# Sheet1-control.net
KiCad netlist of a schematic drawn in Altium Designer
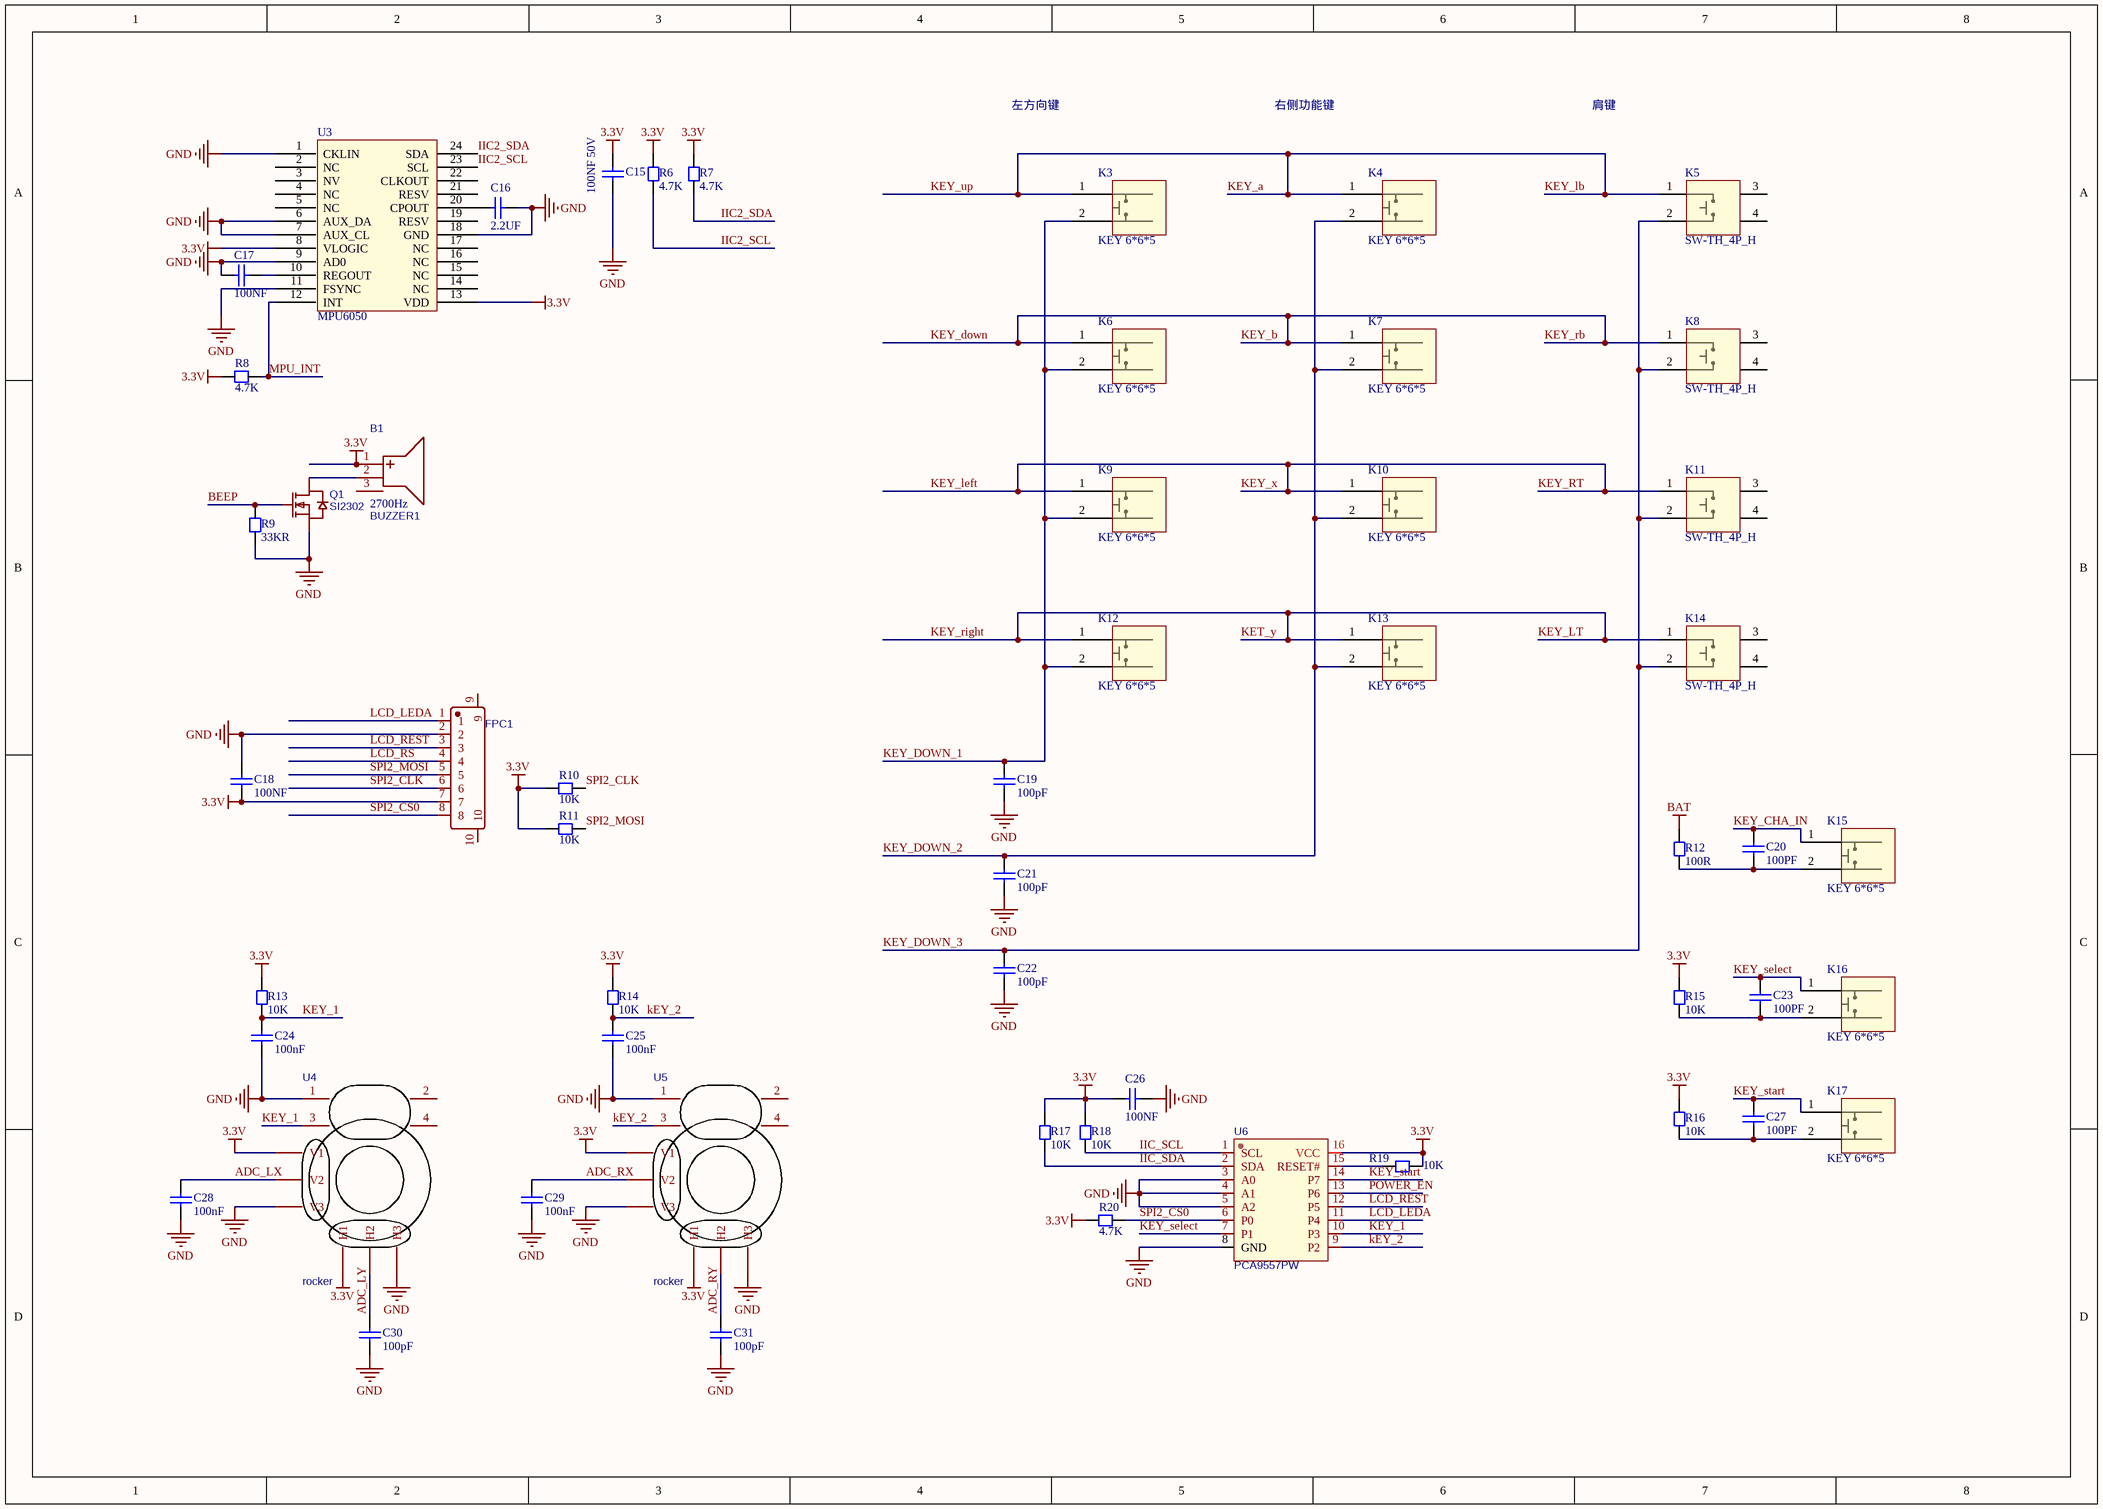
[diagram p0: Sheet1-control.SchDoc]

(export (version "E")
  (design (tool "Eeschema 10.0.6"))
  (components
    (comp (ref "B1")
      (value "BUZZER1")
      (footprint "BUZ-SMD_GSC7525RA")
      (description "2700Hz")
      (fields
        (field (name "MANUFACTURER") "INGHAi(赢海)")
        (field (name "MANUFACTURER PART") "GSC7525RA-16R2700")
        (field (name "CONTRIBUTOR") "LCSC")
      )
      (libsource (lib "base") (part "BUZZER1"))
    )
    (comp (ref "C15")
      (value "100NF 50V")
      (footprint "CC1608-0603")
      (description "0603封装的电容")
      (fields (field (name "PUBLISHER") "Altium Limited"))
      (libsource (lib "base") (part "Cap Chip 0603"))
    )
    (comp (ref "C16")
      (value "2.2UF")
      (footprint "CC1608-0603")
      (description "0603封装的电容")
      (fields (field (name "PUBLISHER") "Altium Limited"))
      (libsource (lib "base") (part "Cap Chip 0603"))
    )
    (comp (ref "C17")
      (value "100NF")
      (footprint "CC1608-0603")
      (description "0603封装的电容")
      (fields (field (name "PUBLISHER") "Altium Limited"))
      (libsource (lib "base") (part "Cap Chip 0603"))
    )
    (comp (ref "C18")
      (value "100NF")
      (footprint "CC1608-0603")
      (description "0603封装的电容")
      (fields (field (name "PUBLISHER") "Altium Limited"))
      (libsource (lib "base") (part "Cap Chip 0603"))
    )
    (comp (ref "C19")
      (value "100pF")
      (footprint "CC1608-0603")
      (description "0603封装的电容")
      (fields (field (name "PUBLISHER") "Altium Limited"))
      (libsource (lib "base") (part "Cap Chip 0603"))
    )
    (comp (ref "C20")
      (value "100PF")
      (footprint "CC1608-0603")
      (description "0603封装的电容")
      (fields (field (name "PUBLISHER") "Altium Limited"))
      (libsource (lib "base") (part "Cap Chip 0603"))
    )
    (comp (ref "C21")
      (value "100pF")
      (footprint "CC1608-0603")
      (description "0603封装的电容")
      (fields (field (name "PUBLISHER") "Altium Limited"))
      (libsource (lib "base") (part "Cap Chip 0603"))
    )
    (comp (ref "C22")
      (value "100pF")
      (footprint "CC1608-0603")
      (description "0603封装的电容")
      (fields (field (name "PUBLISHER") "Altium Limited"))
      (libsource (lib "base") (part "Cap Chip 0603"))
    )
    (comp (ref "C23")
      (value "100PF")
      (footprint "CC1608-0603")
      (description "0603封装的电容")
      (fields (field (name "PUBLISHER") "Altium Limited"))
      (libsource (lib "base") (part "Cap Chip 0603"))
    )
    (comp (ref "C24")
      (value "100nF")
      (footprint "CC1608-0603")
      (description "0603封装的电容")
      (fields (field (name "PUBLISHER") "Altium Limited"))
      (libsource (lib "base") (part "Cap Chip 0603"))
    )
    (comp (ref "C25")
      (value "100nF")
      (footprint "CC1608-0603")
      (description "0603封装的电容")
      (fields (field (name "PUBLISHER") "Altium Limited"))
      (libsource (lib "base") (part "Cap Chip 0603"))
    )
    (comp (ref "C26")
      (value "100NF")
      (footprint "CC1608-0603")
      (description "0603封装的电容")
      (fields (field (name "PUBLISHER") "Altium Limited"))
      (libsource (lib "base") (part "Cap Chip 0603"))
    )
    (comp (ref "C27")
      (value "100PF")
      (footprint "CC1608-0603")
      (description "0603封装的电容")
      (fields (field (name "PUBLISHER") "Altium Limited"))
      (libsource (lib "base") (part "Cap Chip 0603"))
    )
    (comp (ref "C28")
      (value "100nF")
      (footprint "CC1608-0603")
      (description "0603封装的电容")
      (fields (field (name "PUBLISHER") "Altium Limited"))
      (libsource (lib "base") (part "Cap Chip 0603"))
    )
    (comp (ref "C29")
      (value "100nF")
      (footprint "CC1608-0603")
      (description "0603封装的电容")
      (fields (field (name "PUBLISHER") "Altium Limited"))
      (libsource (lib "base") (part "Cap Chip 0603"))
    )
    (comp (ref "C30")
      (value "100pF")
      (footprint "CC1608-0603")
      (description "0603封装的电容")
      (fields (field (name "PUBLISHER") "Altium Limited"))
      (libsource (lib "base") (part "Cap Chip 0603"))
    )
    (comp (ref "C31")
      (value "100pF")
      (footprint "CC1608-0603")
      (description "0603封装的电容")
      (fields (field (name "PUBLISHER") "Altium Limited"))
      (libsource (lib "base") (part "Cap Chip 0603"))
    )
    (comp (ref "FPC1")
      (value "FFC 05 8P")
      (footprint "FFC-SMD_8P-P0.50")
      (fields
        (field (name "MANUFACTURER") "TXGA(特思嘉)")
        (field (name "MANUFACTURER PART") "FFC05001-08SBB124W5M-H")
        (field (name "CONTRIBUTOR") "LCSC")
      )
      (libsource (lib "Connectors") (part "FFC 05 8P"))
    )
    (comp (ref "K3")
      (value "KEY 6*6*5")
      (footprint "KEY 6*6*5")
      (description "无声轻触开关")
      (libsource (lib "base") (part "KEY 6*6*5"))
    )
    (comp (ref "K4")
      (value "KEY 6*6*5")
      (footprint "KEY 6*6*5")
      (description "无声轻触开关")
      (libsource (lib "base") (part "KEY 6*6*5"))
    )
    (comp (ref "K5")
      (value "SW-TH_4P_H")
      (footprint "SW-TH_KH-6X6X7H-ZJ")
      (description "卧式轻触开关")
      (libsource (lib "base") (part "SW-TH_4P_H"))
    )
    (comp (ref "K6")
      (value "KEY 6*6*5")
      (footprint "KEY 6*6*5")
      (description "无声轻触开关")
      (libsource (lib "base") (part "KEY 6*6*5"))
    )
    (comp (ref "K7")
      (value "KEY 6*6*5")
      (footprint "KEY 6*6*5")
      (description "无声轻触开关")
      (libsource (lib "base") (part "KEY 6*6*5"))
    )
    (comp (ref "K8")
      (value "SW-TH_4P_H")
      (footprint "SW-TH_KH-6X6X7H-ZJ")
      (description "卧式轻触开关")
      (libsource (lib "base") (part "SW-TH_4P_H"))
    )
    (comp (ref "K9")
      (value "KEY 6*6*5")
      (footprint "KEY 6*6*5")
      (description "无声轻触开关")
      (libsource (lib "base") (part "KEY 6*6*5"))
    )
    (comp (ref "K10")
      (value "KEY 6*6*5")
      (footprint "KEY 6*6*5")
      (description "无声轻触开关")
      (libsource (lib "base") (part "KEY 6*6*5"))
    )
    (comp (ref "K11")
      (value "SW-TH_4P_H")
      (footprint "SW-TH_KH-6X6X7H-ZJ")
      (description "卧式轻触开关")
      (libsource (lib "base") (part "SW-TH_4P_H"))
    )
    (comp (ref "K12")
      (value "KEY 6*6*5")
      (footprint "KEY 6*6*5")
      (description "无声轻触开关")
      (libsource (lib "base") (part "KEY 6*6*5"))
    )
    (comp (ref "K13")
      (value "KEY 6*6*5")
      (footprint "KEY 6*6*5")
      (description "无声轻触开关")
      (libsource (lib "base") (part "KEY 6*6*5"))
    )
    (comp (ref "K14")
      (value "SW-TH_4P_H")
      (footprint "SW-TH_KH-6X6X7H-ZJ")
      (description "卧式轻触开关")
      (libsource (lib "base") (part "SW-TH_4P_H"))
    )
    (comp (ref "K15")
      (value "KEY 6*6*5")
      (footprint "KEY 6*6*5")
      (description "无声轻触开关")
      (libsource (lib "base") (part "KEY 6*6*5"))
    )
    (comp (ref "K16")
      (value "KEY 6*6*5")
      (footprint "KEY 6*6*5")
      (description "无声轻触开关")
      (libsource (lib "base") (part "KEY 6*6*5"))
    )
    (comp (ref "K17")
      (value "KEY 6*6*5")
      (footprint "KEY 6*6*5")
      (description "无声轻触开关")
      (libsource (lib "base") (part "KEY 6*6*5"))
    )
    (comp (ref "Q1")
      (value "SI2302")
      (footprint "SOT-23")
      (fields
        (field (name "MANUFACTURER") "TWGMC(台湾迪嘉)")
        (field (name "MANUFACTURER PART") "SI2306")
        (field (name "CONTRIBUTOR") "LCSC")
      )
      (libsource (lib "transistor") (part "SI2302"))
    )
    (comp (ref "R6")
      (value "4.7K")
      (footprint "CR1608-0603")
      (description "0603封装电阻")
      (fields (field (name "PUBLISHER") "Altium Limited"))
      (libsource (lib "base") (part "Resistor Chip 0603"))
    )
    (comp (ref "R7")
      (value "4.7K")
      (footprint "CR1608-0603")
      (description "0603封装电阻")
      (fields (field (name "PUBLISHER") "Altium Limited"))
      (libsource (lib "base") (part "Resistor Chip 0603"))
    )
    (comp (ref "R8")
      (value "4.7K")
      (footprint "CR1608-0603")
      (description "0603封装电阻")
      (fields (field (name "PUBLISHER") "Altium Limited"))
      (libsource (lib "") (part "Resistor Chip 0603_2"))
    )
    (comp (ref "R9")
      (value "33KR")
      (footprint "CR1608-0603")
      (description "贴片电阻")
      (libsource (lib "tianxiaohua_Schlib") (part "Chip resistor"))
    )
    (comp (ref "R10")
      (value "10K")
      (footprint "CR1608-0603")
      (description "0603封装电阻")
      (fields (field (name "PUBLISHER") "Altium Limited"))
      (libsource (lib "") (part "Resistor Chip 0603_1"))
    )
    (comp (ref "R11")
      (value "10K")
      (footprint "CR1608-0603")
      (description "0603封装电阻")
      (fields (field (name "PUBLISHER") "Altium Limited"))
      (libsource (lib "") (part "Resistor Chip 0603_1"))
    )
    (comp (ref "R12")
      (value "100R")
      (footprint "CR1608-0603")
      (description "0603封装电阻")
      (fields (field (name "PUBLISHER") "Altium Limited"))
      (libsource (lib "base") (part "Resistor Chip 0603"))
    )
    (comp (ref "R13")
      (value "10K")
      (footprint "CR1608-0603")
      (description "0603封装电阻")
      (fields (field (name "PUBLISHER") "Altium Limited"))
      (libsource (lib "") (part "Resistor Chip 0603_3"))
    )
    (comp (ref "R14")
      (value "10K")
      (footprint "CR1608-0603")
      (description "0603封装电阻")
      (fields (field (name "PUBLISHER") "Altium Limited"))
      (libsource (lib "") (part "Resistor Chip 0603_3"))
    )
    (comp (ref "R15")
      (value "10K")
      (footprint "CR1608-0603")
      (description "0603封装电阻")
      (fields (field (name "PUBLISHER") "Altium Limited"))
      (libsource (lib "base") (part "Resistor Chip 0603"))
    )
    (comp (ref "R16")
      (value "10K")
      (footprint "CR1608-0603")
      (description "0603封装电阻")
      (fields (field (name "PUBLISHER") "Altium Limited"))
      (libsource (lib "base") (part "Resistor Chip 0603"))
    )
    (comp (ref "R17")
      (value "10K")
      (footprint "CR1608-0603")
      (description "0603封装电阻")
      (fields (field (name "PUBLISHER") "Altium Limited"))
      (libsource (lib "base") (part "Resistor Chip 0603"))
    )
    (comp (ref "R18")
      (value "10K")
      (footprint "CR1608-0603")
      (description "0603封装电阻")
      (fields (field (name "PUBLISHER") "Altium Limited"))
      (libsource (lib "base") (part "Resistor Chip 0603"))
    )
    (comp (ref "R19")
      (value "10K")
      (footprint "CR1608-0603")
      (description "0603封装电阻")
      (fields (field (name "PUBLISHER") "Altium Limited"))
      (libsource (lib "") (part "Resistor Chip 0603_1"))
    )
    (comp (ref "R20")
      (value "4.7K")
      (footprint "CR1608-0603")
      (description "0603封装电阻")
      (fields (field (name "PUBLISHER") "Altium Limited"))
      (libsource (lib "") (part "Resistor Chip 0603_2"))
    )
    (comp (ref "U3")
      (value "MPU6050")
      (footprint "QFN24 - duplicate")
      (description "陀螺仪")
      (libsource (lib "sensor") (part "MPU6050"))
    )
    (comp (ref "U4")
      (value "rocker")
      (footprint "PCBComponent_1")
      (fields (field (name "MANUFACTURER PART") "摇杆") (field (name "CONTRIBUTOR") "Alex_Ai"))
      (libsource (lib "base") (part "rocker"))
    )
    (comp (ref "U5")
      (value "rocker")
      (footprint "PCBComponent_1")
      (fields (field (name "MANUFACTURER PART") "摇杆") (field (name "CONTRIBUTOR") "Alex_Ai"))
      (libsource (lib "base") (part "rocker"))
    )
    (comp (ref "U6")
      (value "PCA9557PW")
      (footprint "TSSOP-16")
      (description "TSSOP-16 8位I2C总线和SMBus I/O扩展器芯片")
      (fields (field (name "MANUFACTURER") "TI(德州仪器)") (field (name "CONTRIBUTOR") "LCSC"))
      (libsource (lib "PB-Chip") (part "PCA9557PW"))
    )
  )
  (nets
    (net (code "1") (name "/ADC_LX") (class "Default")
      (node (ref "C28") (pin "2") (pinfunction "2_2") (pintype "passive"))
      (node (ref "U4") (pin "6") (pinfunction "V2_6") (pintype "passive"))
    )
    (net (code "2") (name "/ADC_LY") (class "Default")
      (node (ref "C30") (pin "2") (pinfunction "2_2") (pintype "passive"))
      (node (ref "U4") (pin "9") (pinfunction "H2_9") (pintype "passive"))
    )
    (net (code "3") (name "/ADC_RX") (class "Default")
      (node (ref "C29") (pin "2") (pinfunction "2_2") (pintype "passive"))
      (node (ref "U5") (pin "6") (pinfunction "V2_6") (pintype "passive"))
    )
    (net (code "4") (name "/ADC_RY") (class "Default")
      (node (ref "C31") (pin "2") (pinfunction "2_2") (pintype "passive"))
      (node (ref "U5") (pin "9") (pinfunction "H2_9") (pintype "passive"))
    )
    (net (code "5") (name "/BEEP") (class "Default")
      (node (ref "Q1") (pin "1") (pinfunction "G_1") (pintype "passive"))
      (node (ref "R9") (pin "1") (pinfunction "1_1") (pintype "passive"))
    )
    (net (code "6") (name "/IIC2_SCL") (class "Default")
      (node (ref "R6") (pin "2") (pinfunction "2_2") (pintype "passive"))
      (node (ref "U3") (pin "23") (pinfunction "SCL_23") (pintype "passive"))
    )
    (net (code "7") (name "/IIC2_SDA") (class "Default")
      (node (ref "R7") (pin "2") (pinfunction "2_2") (pintype "passive"))
      (node (ref "U3") (pin "24") (pinfunction "SDA_24") (pintype "passive"))
    )
    (net (code "8") (name "/IIC_SCL") (class "Default")
      (node (ref "R18") (pin "2") (pinfunction "2_2") (pintype "passive"))
      (node (ref "U6") (pin "1") (pinfunction "SCL_1") (pintype "passive"))
    )
    (net (code "9") (name "/IIC_SDA") (class "Default")
      (node (ref "R17") (pin "2") (pinfunction "2_2") (pintype "passive"))
      (node (ref "U6") (pin "2") (pinfunction "SDA_2") (pintype "passive"))
    )
    (net (code "10") (name "/KET_y") (class "Default")
      (node (ref "K12") (pin "1") (pinfunction "1_1") (pintype "passive"))
      (node (ref "K13") (pin "1") (pinfunction "1_1") (pintype "passive"))
      (node (ref "K14") (pin "1") (pinfunction "1_1") (pintype "passive"))
    )
    (net (code "11") (name "/KEY_1") (class "Default")
      (node (ref "C24") (pin "2") (pinfunction "2_2") (pintype "passive"))
      (node (ref "R13") (pin "1") (pinfunction "1_1") (pintype "passive"))
      (node (ref "U4") (pin "3") (pinfunction "3_3") (pintype "passive"))
      (node (ref "U6") (pin "10") (pinfunction "P3_10") (pintype "passive"))
    )
    (net (code "12") (name "/KEY_CHA_IN") (class "Default")
      (node (ref "C20") (pin "1") (pinfunction "1_1") (pintype "passive"))
      (node (ref "K15") (pin "1") (pinfunction "1_1") (pintype "passive"))
    )
    (net (code "13") (name "/KEY_DOWN_1") (class "Default")
      (node (ref "C19") (pin "2") (pinfunction "2_2") (pintype "passive"))
      (node (ref "K12") (pin "2") (pinfunction "2_2") (pintype "passive"))
      (node (ref "K3") (pin "2") (pinfunction "2_2") (pintype "passive"))
      (node (ref "K6") (pin "2") (pinfunction "2_2") (pintype "passive"))
      (node (ref "K9") (pin "2") (pinfunction "2_2") (pintype "passive"))
    )
    (net (code "14") (name "/KEY_DOWN_2") (class "Default")
      (node (ref "C21") (pin "2") (pinfunction "2_2") (pintype "passive"))
      (node (ref "K10") (pin "2") (pinfunction "2_2") (pintype "passive"))
      (node (ref "K13") (pin "2") (pinfunction "2_2") (pintype "passive"))
      (node (ref "K4") (pin "2") (pinfunction "2_2") (pintype "passive"))
      (node (ref "K7") (pin "2") (pinfunction "2_2") (pintype "passive"))
    )
    (net (code "15") (name "/KEY_DOWN_3") (class "Default")
      (node (ref "C22") (pin "2") (pinfunction "2_2") (pintype "passive"))
      (node (ref "K11") (pin "2") (pinfunction "2_2") (pintype "passive"))
      (node (ref "K14") (pin "2") (pinfunction "2_2") (pintype "passive"))
      (node (ref "K5") (pin "2") (pinfunction "2_2") (pintype "passive"))
      (node (ref "K8") (pin "2") (pinfunction "2_2") (pintype "passive"))
    )
    (net (code "16") (name "/KEY_RT") (class "Default")
      (node (ref "K10") (pin "1") (pinfunction "1_1") (pintype "passive"))
      (node (ref "K11") (pin "1") (pinfunction "1_1") (pintype "passive"))
      (node (ref "K9") (pin "1") (pinfunction "1_1") (pintype "passive"))
    )
    (net (code "17") (name "/KEY_a") (class "Default")
      (node (ref "K3") (pin "1") (pinfunction "1_1") (pintype "passive"))
      (node (ref "K4") (pin "1") (pinfunction "1_1") (pintype "passive"))
      (node (ref "K5") (pin "1") (pinfunction "1_1") (pintype "passive"))
    )
    (net (code "18") (name "/KEY_b") (class "Default")
      (node (ref "K6") (pin "1") (pinfunction "1_1") (pintype "passive"))
      (node (ref "K7") (pin "1") (pinfunction "1_1") (pintype "passive"))
      (node (ref "K8") (pin "1") (pinfunction "1_1") (pintype "passive"))
    )
    (net (code "19") (name "/KEY_select") (class "Default")
      (node (ref "C23") (pin "1") (pinfunction "1_1") (pintype "passive"))
      (node (ref "K16") (pin "1") (pinfunction "1_1") (pintype "passive"))
      (node (ref "U6") (pin "7") (pinfunction "P1_7") (pintype "passive"))
    )
    (net (code "20") (name "/KEY_start") (class "Default")
      (node (ref "C27") (pin "1") (pinfunction "1_1") (pintype "passive"))
      (node (ref "K17") (pin "1") (pinfunction "1_1") (pintype "passive"))
      (node (ref "U6") (pin "14") (pinfunction "P7_14") (pintype "passive"))
    )
    (net (code "21") (name "/LCD_LEDA") (class "Default")
      (node (ref "FPC1") (pin "1") (pinfunction "1_1") (pintype "passive"))
      (node (ref "U6") (pin "11") (pinfunction "P4_11") (pintype "passive"))
    )
    (net (code "22") (name "/LCD_REST") (class "Default")
      (node (ref "FPC1") (pin "3") (pinfunction "3_3") (pintype "passive"))
      (node (ref "U6") (pin "12") (pinfunction "P5_12") (pintype "passive"))
    )
    (net (code "23") (name "/LCD_RS") (class "Default")
      (node (ref "FPC1") (pin "4") (pinfunction "4_4") (pintype "passive"))
    )
    (net (code "24") (name "/MPU_INT") (class "Default")
      (node (ref "R8") (pin "2") (pinfunction "2_2") (pintype "passive"))
      (node (ref "U3") (pin "12") (pinfunction "INT_12") (pintype "passive"))
    )
    (net (code "25") (name "/POWER_EN") (class "Default")
      (node (ref "U6") (pin "13") (pinfunction "P6_13") (pintype "passive"))
    )
    (net (code "26") (name "/SPI2_CLK") (class "Default")
      (node (ref "FPC1") (pin "6") (pinfunction "6_6") (pintype "passive"))
      (node (ref "R10") (pin "1") (pinfunction "1_1") (pintype "passive"))
    )
    (net (code "27") (name "/SPI2_CS0") (class "Default")
      (node (ref "FPC1") (pin "8") (pinfunction "8_8") (pintype "passive"))
      (node (ref "R20") (pin "2") (pinfunction "2_2") (pintype "passive"))
      (node (ref "U6") (pin "6") (pinfunction "P0_6") (pintype "passive"))
    )
    (net (code "28") (name "/SPI2_MOSI") (class "Default")
      (node (ref "FPC1") (pin "5") (pinfunction "5_5") (pintype "passive"))
      (node (ref "R11") (pin "1") (pinfunction "1_1") (pintype "passive"))
    )
    (net (code "29") (name "/kEY_2") (class "Default")
      (node (ref "C25") (pin "2") (pinfunction "2_2") (pintype "passive"))
      (node (ref "R14") (pin "1") (pinfunction "1_1") (pintype "passive"))
      (node (ref "U5") (pin "3") (pinfunction "3_3") (pintype "passive"))
      (node (ref "U6") (pin "9") (pinfunction "P2_9") (pintype "passive"))
    )
    (net (code "30") (name "3.3V") (class "Default")
      (node (ref "B1") (pin "1") (pinfunction "+_1") (pintype "passive"))
      (node (ref "C15") (pin "2") (pinfunction "2_2") (pintype "passive"))
      (node (ref "C18") (pin "1") (pinfunction "1_1") (pintype "passive"))
      (node (ref "C26") (pin "2") (pinfunction "2_2") (pintype "passive"))
      (node (ref "FPC1") (pin "7") (pinfunction "7_7") (pintype "passive"))
      (node (ref "R10") (pin "2") (pinfunction "2_2") (pintype "passive"))
      (node (ref "R11") (pin "2") (pinfunction "2_2") (pintype "passive"))
      (node (ref "R13") (pin "2") (pinfunction "2_2") (pintype "passive"))
      (node (ref "R14") (pin "2") (pinfunction "2_2") (pintype "passive"))
      (node (ref "R15") (pin "1") (pinfunction "1_1") (pintype "passive"))
      (node (ref "R16") (pin "1") (pinfunction "1_1") (pintype "passive"))
      (node (ref "R17") (pin "1") (pinfunction "1_1") (pintype "passive"))
      (node (ref "R18") (pin "1") (pinfunction "1_1") (pintype "passive"))
      (node (ref "R19") (pin "1") (pinfunction "1_1") (pintype "passive"))
      (node (ref "R20") (pin "1") (pinfunction "1_1") (pintype "passive"))
      (node (ref "R6") (pin "1") (pinfunction "1_1") (pintype "passive"))
      (node (ref "R7") (pin "1") (pinfunction "1_1") (pintype "passive"))
      (node (ref "R8") (pin "1") (pinfunction "1_1") (pintype "passive"))
      (node (ref "U3") (pin "13") (pinfunction "VDD_13") (pintype "passive"))
      (node (ref "U3") (pin "8") (pinfunction "VLOGIC_8") (pintype "passive"))
      (node (ref "U4") (pin "5") (pinfunction "V1_5") (pintype "passive"))
      (node (ref "U4") (pin "8") (pinfunction "H1_8") (pintype "passive"))
      (node (ref "U5") (pin "5") (pinfunction "V1_5") (pintype "passive"))
      (node (ref "U5") (pin "8") (pinfunction "H1_8") (pintype "passive"))
      (node (ref "U6") (pin "16") (pinfunction "VCC_16") (pintype "passive"))
    )
    (net (code "31") (name "BAT") (class "Default")
      (node (ref "R12") (pin "1") (pinfunction "1_1") (pintype "passive"))
    )
    (net (code "32") (name "GND") (class "Default")
      (node (ref "C15") (pin "1") (pinfunction "1_1") (pintype "passive"))
      (node (ref "C16") (pin "2") (pinfunction "2_2") (pintype "passive"))
      (node (ref "C17") (pin "1") (pinfunction "1_1") (pintype "passive"))
      (node (ref "C18") (pin "2") (pinfunction "2_2") (pintype "passive"))
      (node (ref "C19") (pin "1") (pinfunction "1_1") (pintype "passive"))
      (node (ref "C21") (pin "1") (pinfunction "1_1") (pintype "passive"))
      (node (ref "C22") (pin "1") (pinfunction "1_1") (pintype "passive"))
      (node (ref "C24") (pin "1") (pinfunction "1_1") (pintype "passive"))
      (node (ref "C25") (pin "1") (pinfunction "1_1") (pintype "passive"))
      (node (ref "C26") (pin "1") (pinfunction "1_1") (pintype "passive"))
      (node (ref "C28") (pin "1") (pinfunction "1_1") (pintype "passive"))
      (node (ref "C29") (pin "1") (pinfunction "1_1") (pintype "passive"))
      (node (ref "C30") (pin "1") (pinfunction "1_1") (pintype "passive"))
      (node (ref "C31") (pin "1") (pinfunction "1_1") (pintype "passive"))
      (node (ref "FPC1") (pin "2") (pinfunction "2_2") (pintype "passive"))
      (node (ref "Q1") (pin "2") (pinfunction "S_2") (pintype "passive"))
      (node (ref "R9") (pin "2") (pinfunction "2_2") (pintype "passive"))
      (node (ref "U3") (pin "1") (pinfunction "CKLIN_1") (pintype "passive"))
      (node (ref "U3") (pin "11") (pinfunction "FSYNC_11") (pintype "passive"))
      (node (ref "U3") (pin "18") (pinfunction "GND_18") (pintype "passive"))
      (node (ref "U3") (pin "6") (pinfunction "AUX_DA_6") (pintype "passive"))
      (node (ref "U3") (pin "7") (pinfunction "AUX_CL_7") (pintype "passive"))
      (node (ref "U3") (pin "9") (pinfunction "AD0_9") (pintype "passive"))
      (node (ref "U4") (pin "1") (pinfunction "1_1") (pintype "passive"))
      (node (ref "U4") (pin "10") (pinfunction "H3_10") (pintype "passive"))
      (node (ref "U4") (pin "7") (pinfunction "V3_7") (pintype "passive"))
      (node (ref "U5") (pin "1") (pinfunction "1_1") (pintype "passive"))
      (node (ref "U5") (pin "10") (pinfunction "H3_10") (pintype "passive"))
      (node (ref "U5") (pin "7") (pinfunction "V3_7") (pintype "passive"))
      (node (ref "U6") (pin "3") (pinfunction "A0_3") (pintype "passive"))
      (node (ref "U6") (pin "4") (pinfunction "A1_4") (pintype "passive"))
      (node (ref "U6") (pin "5") (pinfunction "A2_5") (pintype "passive"))
      (node (ref "U6") (pin "8") (pinfunction "GND_8") (pintype "passive"))
    )
    (net (code "33") (name "Net-(B1--)") (class "Default")
      (node (ref "B1") (pin "2") (pinfunction "-_2") (pintype "passive"))
      (node (ref "Q1") (pin "3") (pinfunction "D_3") (pintype "passive"))
    )
    (net (code "34") (name "Net-(C20-Pad2)") (class "Default")
      (node (ref "C20") (pin "2") (pinfunction "2_2") (pintype "passive"))
      (node (ref "K15") (pin "2") (pinfunction "2_2") (pintype "passive"))
      (node (ref "R12") (pin "2") (pinfunction "2_2") (pintype "passive"))
    )
    (net (code "35") (name "Net-(C23-Pad2)") (class "Default")
      (node (ref "C23") (pin "2") (pinfunction "2_2") (pintype "passive"))
      (node (ref "K16") (pin "2") (pinfunction "2_2") (pintype "passive"))
      (node (ref "R15") (pin "2") (pinfunction "2_2") (pintype "passive"))
    )
    (net (code "36") (name "Net-(C27-Pad2)") (class "Default")
      (node (ref "C27") (pin "2") (pinfunction "2_2") (pintype "passive"))
      (node (ref "K17") (pin "2") (pinfunction "2_2") (pintype "passive"))
      (node (ref "R16") (pin "2") (pinfunction "2_2") (pintype "passive"))
    )
    (net (code "37") (name "Net-(U3-CPOUT)") (class "Default")
      (node (ref "C16") (pin "1") (pinfunction "1_1") (pintype "passive"))
      (node (ref "U3") (pin "20") (pinfunction "CPOUT_20") (pintype "passive"))
    )
    (net (code "38") (name "Net-(U3-REGOUT)") (class "Default")
      (node (ref "C17") (pin "2") (pinfunction "2_2") (pintype "passive"))
      (node (ref "U3") (pin "10") (pinfunction "REGOUT_10") (pintype "passive"))
    )
    (net (code "39") (name "Net-(U6-RESET#)") (class "Default")
      (node (ref "R19") (pin "2") (pinfunction "2_2") (pintype "passive"))
      (node (ref "U6") (pin "15") (pinfunction "RESET#_15") (pintype "passive"))
    )
    (net (code "40") (name "unconnected-(B1-EH-Pad3)") (class "Default")
      (node (ref "B1") (pin "3") (pinfunction "EH_3") (pintype "passive"))
    )
    (net (code "41") (name "unconnected-(FPC1-Pad9)") (class "Default")
      (node (ref "FPC1") (pin "9") (pinfunction "9_9") (pintype "passive"))
    )
    (net (code "42") (name "unconnected-(FPC1-Pad10)") (class "Default")
      (node (ref "FPC1") (pin "10") (pinfunction "10_10") (pintype "passive"))
    )
    (net (code "43") (name "unconnected-(K5-Pad3)") (class "Default")
      (node (ref "K5") (pin "3") (pinfunction "3_3") (pintype "passive"))
    )
    (net (code "44") (name "unconnected-(K5-Pad4)") (class "Default")
      (node (ref "K5") (pin "4") (pinfunction "4_4") (pintype "passive"))
    )
    (net (code "45") (name "unconnected-(K8-Pad3)") (class "Default")
      (node (ref "K8") (pin "3") (pinfunction "3_3") (pintype "passive"))
    )
    (net (code "46") (name "unconnected-(K8-Pad4)") (class "Default")
      (node (ref "K8") (pin "4") (pinfunction "4_4") (pintype "passive"))
    )
    (net (code "47") (name "unconnected-(K11-Pad3)") (class "Default")
      (node (ref "K11") (pin "3") (pinfunction "3_3") (pintype "passive"))
    )
    (net (code "48") (name "unconnected-(K11-Pad4)") (class "Default")
      (node (ref "K11") (pin "4") (pinfunction "4_4") (pintype "passive"))
    )
    (net (code "49") (name "unconnected-(K14-Pad3)") (class "Default")
      (node (ref "K14") (pin "3") (pinfunction "3_3") (pintype "passive"))
    )
    (net (code "50") (name "unconnected-(K14-Pad4)") (class "Default")
      (node (ref "K14") (pin "4") (pinfunction "4_4") (pintype "passive"))
    )
    (net (code "51") (name "unconnected-(U3-CLKOUT-Pad22)") (class "Default")
      (node (ref "U3") (pin "22") (pinfunction "CLKOUT_22") (pintype "passive"))
    )
    (net (code "52") (name "unconnected-(U3-NC-Pad2)") (class "Default")
      (node (ref "U3") (pin "2") (pinfunction "NC_2") (pintype "passive"))
    )
    (net (code "53") (name "unconnected-(U3-NC-Pad4)") (class "Default")
      (node (ref "U3") (pin "4") (pinfunction "NC_4") (pintype "passive"))
    )
    (net (code "54") (name "unconnected-(U3-NC-Pad5)") (class "Default")
      (node (ref "U3") (pin "5") (pinfunction "NC_5") (pintype "passive"))
    )
    (net (code "55") (name "unconnected-(U3-NC-Pad14)") (class "Default")
      (node (ref "U3") (pin "14") (pinfunction "NC_14") (pintype "passive"))
    )
    (net (code "56") (name "unconnected-(U3-NC-Pad15)") (class "Default")
      (node (ref "U3") (pin "15") (pinfunction "NC_15") (pintype "passive"))
    )
    (net (code "57") (name "unconnected-(U3-NC-Pad16)") (class "Default")
      (node (ref "U3") (pin "16") (pinfunction "NC_16") (pintype "passive"))
    )
    (net (code "58") (name "unconnected-(U3-NC-Pad17)") (class "Default")
      (node (ref "U3") (pin "17") (pinfunction "NC_17") (pintype "passive"))
    )
    (net (code "59") (name "unconnected-(U3-NV-Pad3)") (class "Default")
      (node (ref "U3") (pin "3") (pinfunction "NV_3") (pintype "passive"))
    )
    (net (code "60") (name "unconnected-(U3-RESV-Pad19)") (class "Default")
      (node (ref "U3") (pin "19") (pinfunction "RESV_19") (pintype "passive"))
    )
    (net (code "61") (name "unconnected-(U3-RESV-Pad21)") (class "Default")
      (node (ref "U3") (pin "21") (pinfunction "RESV_21") (pintype "passive"))
    )
    (net (code "62") (name "unconnected-(U4-Pad2)") (class "Default")
      (node (ref "U4") (pin "2") (pinfunction "2_2") (pintype "passive"))
    )
    (net (code "63") (name "unconnected-(U4-Pad4)") (class "Default")
      (node (ref "U4") (pin "4") (pinfunction "4_4") (pintype "passive"))
    )
    (net (code "64") (name "unconnected-(U5-Pad2)") (class "Default")
      (node (ref "U5") (pin "2") (pinfunction "2_2") (pintype "passive"))
    )
    (net (code "65") (name "unconnected-(U5-Pad4)") (class "Default")
      (node (ref "U5") (pin "4") (pinfunction "4_4") (pintype "passive"))
    )
  )
)
